# Power.net
KiCad netlist of a schematic drawn in Altium Designer
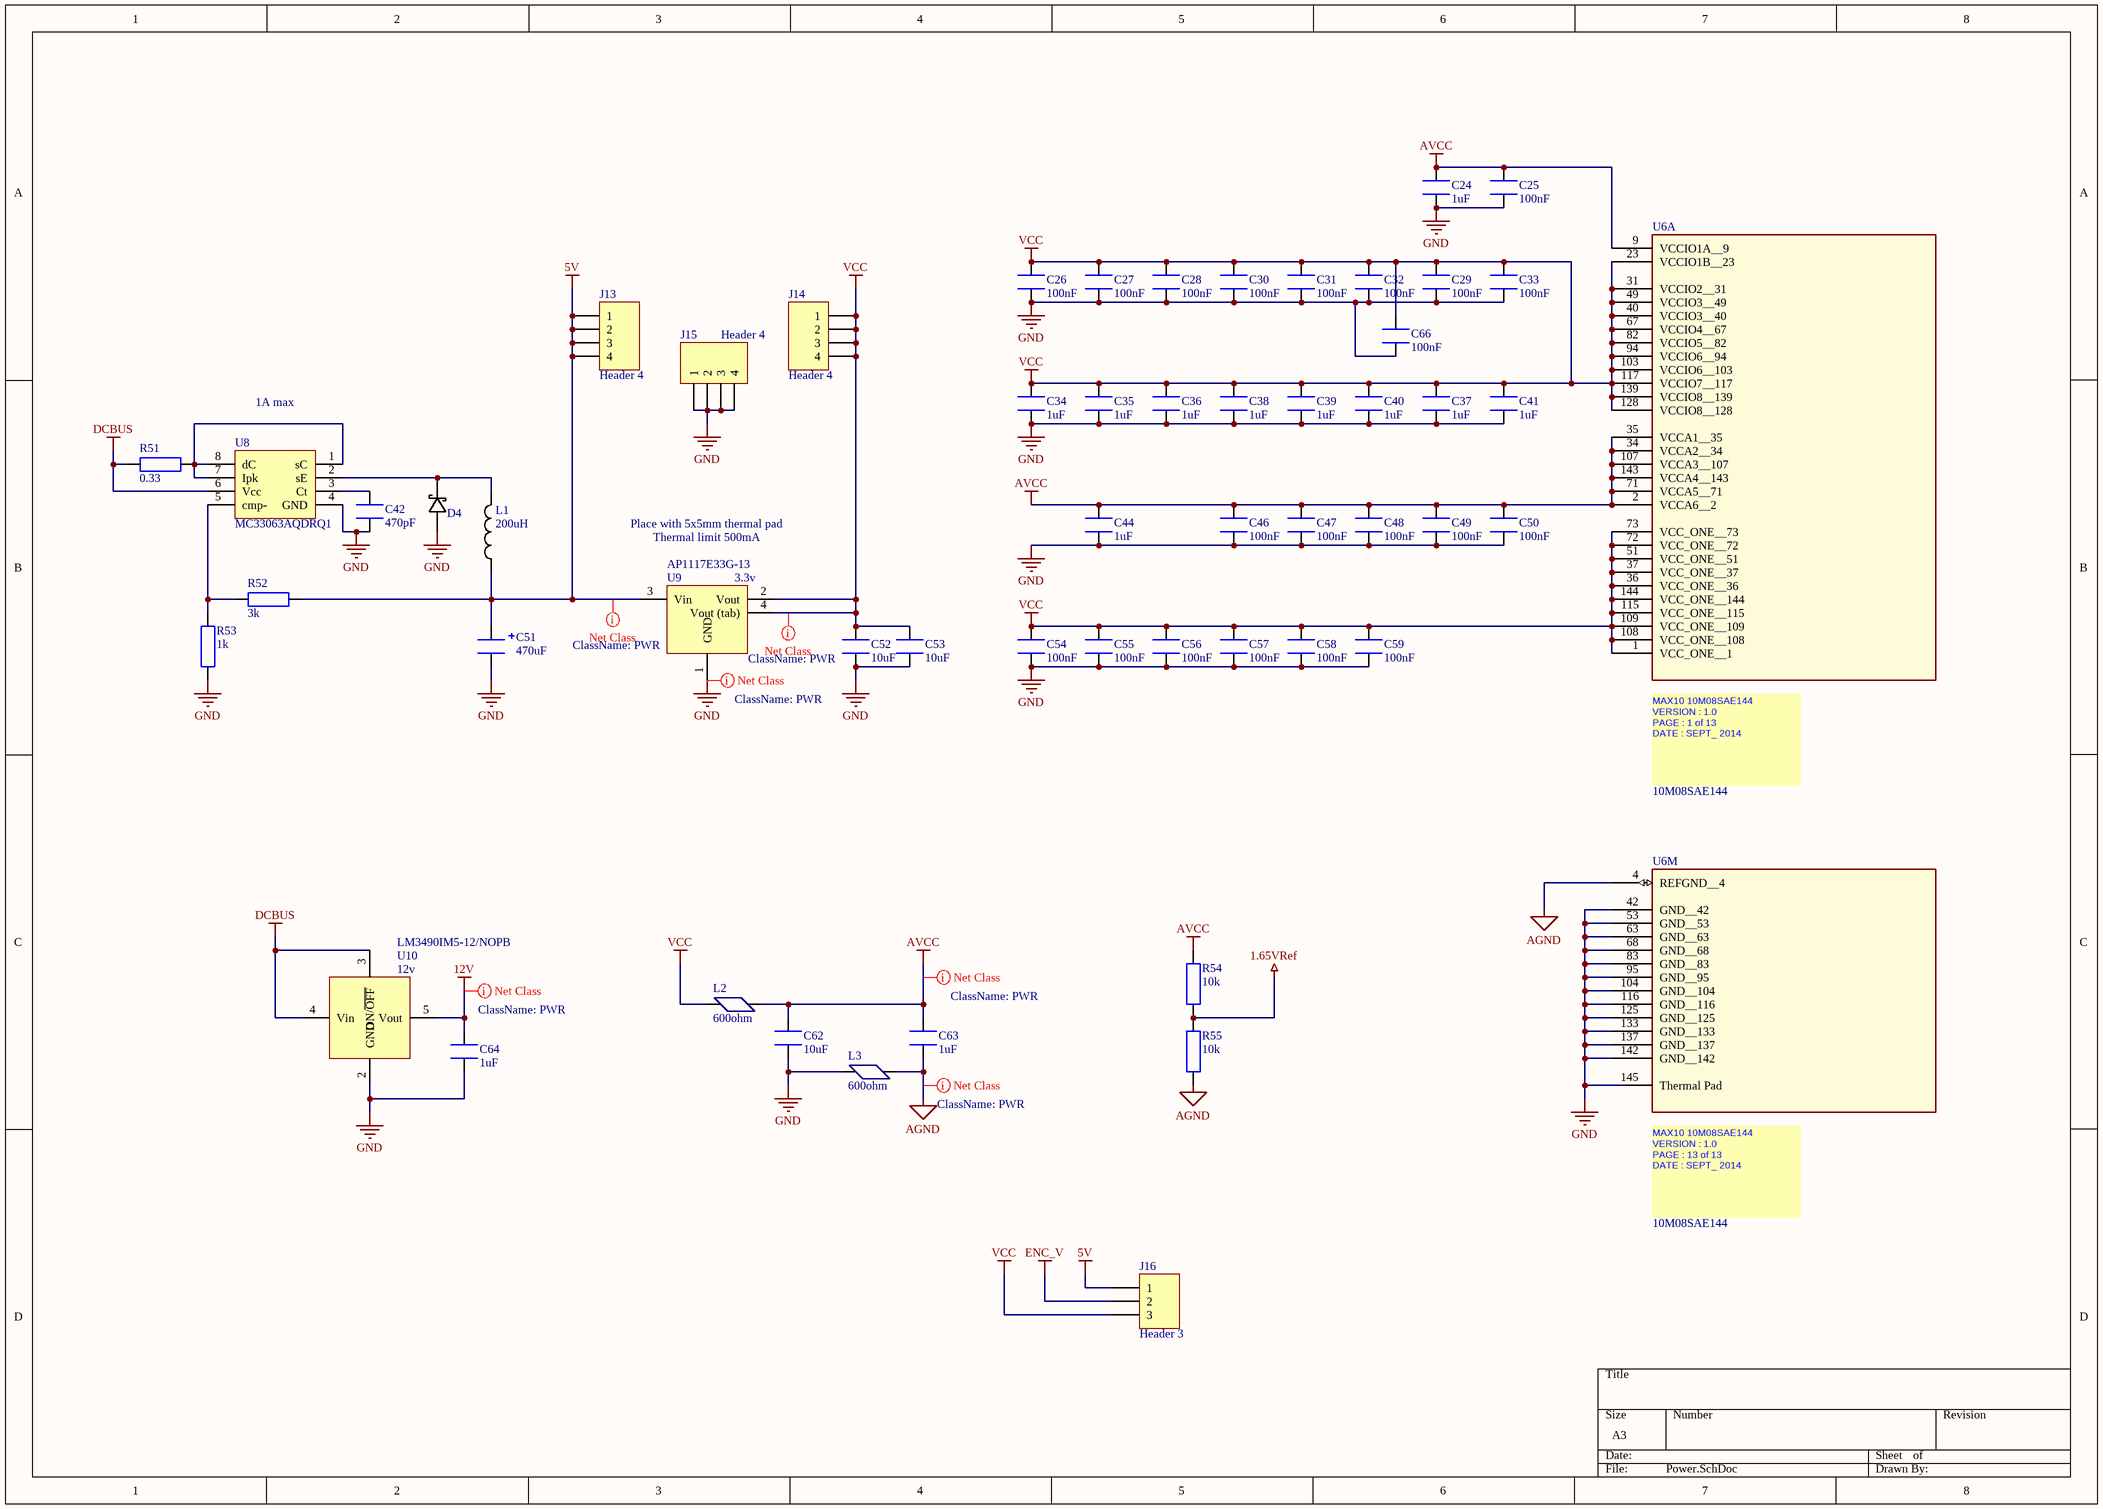
[diagram p0: Power.SchDoc]

(export (version "E")
  (design (tool "Eeschema 10.0.6"))
  (components
    (comp (ref "C24")
      (value "1uF")
      (footprint "1608[0603]")
      (description "CAP, MLCC, X5R, 1UF, 16V, 0603")
      (fields (field (name "Comment") "MC0603X105K160"))
      (libsource (lib "CustomComponents") (part "MC0603X105K160"))
    )
    (comp (ref "C25")
      (value "100nF")
      (footprint "1608[0603]")
      (description "CAP, MLCC, X7R, 100NF, 16V, 0603")
      (fields (field (name "Comment") "MC0603B104K160CT"))
      (libsource (lib "CustomComponents") (part "MC0603B104K160CT"))
    )
    (comp (ref "C26")
      (value "100nF")
      (footprint "1608[0603]")
      (description "CAP, MLCC, X7R, 100NF, 16V, 0603")
      (fields (field (name "Comment") "MC0603B104K160CT"))
      (libsource (lib "CustomComponents") (part "MC0603B104K160CT"))
    )
    (comp (ref "C27")
      (value "100nF")
      (footprint "1608[0603]")
      (description "CAP, MLCC, X7R, 100NF, 16V, 0603")
      (fields (field (name "Comment") "MC0603B104K160CT"))
      (libsource (lib "CustomComponents") (part "MC0603B104K160CT"))
    )
    (comp (ref "C28")
      (value "100nF")
      (footprint "1608[0603]")
      (description "CAP, MLCC, X7R, 100NF, 16V, 0603")
      (fields (field (name "Comment") "MC0603B104K160CT"))
      (libsource (lib "CustomComponents") (part "MC0603B104K160CT"))
    )
    (comp (ref "C29")
      (value "100nF")
      (footprint "1608[0603]")
      (description "CAP, MLCC, X7R, 100NF, 16V, 0603")
      (fields (field (name "Comment") "MC0603B104K160CT"))
      (libsource (lib "CustomComponents") (part "MC0603B104K160CT"))
    )
    (comp (ref "C30")
      (value "100nF")
      (footprint "1608[0603]")
      (description "CAP, MLCC, X7R, 100NF, 16V, 0603")
      (fields (field (name "Comment") "MC0603B104K160CT"))
      (libsource (lib "CustomComponents") (part "MC0603B104K160CT"))
    )
    (comp (ref "C31")
      (value "100nF")
      (footprint "1608[0603]")
      (description "CAP, MLCC, X7R, 100NF, 16V, 0603")
      (fields (field (name "Comment") "MC0603B104K160CT"))
      (libsource (lib "CustomComponents") (part "MC0603B104K160CT"))
    )
    (comp (ref "C32")
      (value "100nF")
      (footprint "1608[0603]")
      (description "CAP, MLCC, X7R, 100NF, 16V, 0603")
      (fields (field (name "Comment") "MC0603B104K160CT"))
      (libsource (lib "CustomComponents") (part "MC0603B104K160CT"))
    )
    (comp (ref "C33")
      (value "100nF")
      (footprint "1608[0603]")
      (description "CAP, MLCC, X7R, 100NF, 16V, 0603")
      (fields (field (name "Comment") "MC0603B104K160CT"))
      (libsource (lib "CustomComponents") (part "MC0603B104K160CT"))
    )
    (comp (ref "C34")
      (value "1uF")
      (footprint "1608[0603]")
      (description "CAP, MLCC, X5R, 1UF, 16V, 0603")
      (fields (field (name "Comment") "MC0603X105K160"))
      (libsource (lib "CustomComponents") (part "MC0603X105K160"))
    )
    (comp (ref "C35")
      (value "1uF")
      (footprint "1608[0603]")
      (description "CAP, MLCC, X5R, 1UF, 16V, 0603")
      (fields (field (name "Comment") "MC0603X105K160"))
      (libsource (lib "CustomComponents") (part "MC0603X105K160"))
    )
    (comp (ref "C36")
      (value "1uF")
      (footprint "1608[0603]")
      (description "CAP, MLCC, X5R, 1UF, 16V, 0603")
      (fields (field (name "Comment") "MC0603X105K160"))
      (libsource (lib "CustomComponents") (part "MC0603X105K160"))
    )
    (comp (ref "C37")
      (value "1uF")
      (footprint "1608[0603]")
      (description "CAP, MLCC, X5R, 1UF, 16V, 0603")
      (fields (field (name "Comment") "MC0603X105K160"))
      (libsource (lib "CustomComponents") (part "MC0603X105K160"))
    )
    (comp (ref "C38")
      (value "1uF")
      (footprint "1608[0603]")
      (description "CAP, MLCC, X5R, 1UF, 16V, 0603")
      (fields (field (name "Comment") "MC0603X105K160"))
      (libsource (lib "CustomComponents") (part "MC0603X105K160"))
    )
    (comp (ref "C39")
      (value "1uF")
      (footprint "1608[0603]")
      (description "CAP, MLCC, X5R, 1UF, 16V, 0603")
      (fields (field (name "Comment") "MC0603X105K160"))
      (libsource (lib "CustomComponents") (part "MC0603X105K160"))
    )
    (comp (ref "C40")
      (value "1uF")
      (footprint "1608[0603]")
      (description "CAP, MLCC, X5R, 1UF, 16V, 0603")
      (fields (field (name "Comment") "MC0603X105K160"))
      (libsource (lib "CustomComponents") (part "MC0603X105K160"))
    )
    (comp (ref "C41")
      (value "1uF")
      (footprint "1608[0603]")
      (description "CAP, MLCC, X5R, 1UF, 16V, 0603")
      (fields (field (name "Comment") "MC0603X105K160"))
      (libsource (lib "CustomComponents") (part "MC0603X105K160"))
    )
    (comp (ref "C42")
      (value "470pF")
      (footprint "1608[0603]")
      (description "CAP, MLCC, X7R, 470PF, 50V, 0603")
      (fields (field (name "Comment") "MC0603B471K500CT"))
      (libsource (lib "CustomComponents") (part "MC0603B471K500CT"))
    )
    (comp (ref "C44")
      (value "1uF")
      (footprint "1608[0603]")
      (description "CAP, MLCC, X5R, 1UF, 16V, 0603")
      (fields (field (name "Comment") "MC0603X105K160"))
      (libsource (lib "CustomComponents") (part "MC0603X105K160"))
    )
    (comp (ref "C46")
      (value "100nF")
      (footprint "1608[0603]")
      (description "CAP, MLCC, X7R, 100NF, 16V, 0603")
      (fields (field (name "Comment") "MC0603B104K160CT"))
      (libsource (lib "CustomComponents") (part "MC0603B104K160CT"))
    )
    (comp (ref "C47")
      (value "100nF")
      (footprint "1608[0603]")
      (description "CAP, MLCC, X7R, 100NF, 16V, 0603")
      (fields (field (name "Comment") "MC0603B104K160CT"))
      (libsource (lib "CustomComponents") (part "MC0603B104K160CT"))
    )
    (comp (ref "C48")
      (value "100nF")
      (footprint "1608[0603]")
      (description "CAP, MLCC, X7R, 100NF, 16V, 0603")
      (fields (field (name "Comment") "MC0603B104K160CT"))
      (libsource (lib "CustomComponents") (part "MC0603B104K160CT"))
    )
    (comp (ref "C49")
      (value "100nF")
      (footprint "1608[0603]")
      (description "CAP, MLCC, X7R, 100NF, 16V, 0603")
      (fields (field (name "Comment") "MC0603B104K160CT"))
      (libsource (lib "CustomComponents") (part "MC0603B104K160CT"))
    )
    (comp (ref "C50")
      (value "100nF")
      (footprint "1608[0603]")
      (description "CAP, MLCC, X7R, 100NF, 16V, 0603")
      (fields (field (name "Comment") "MC0603B104K160CT"))
      (libsource (lib "CustomComponents") (part "MC0603B104K160CT"))
    )
    (comp (ref "C51")
      (value "470uF")
      (footprint "CAP_ELEC_SIZE_G")
      (description "CAP, ALU ELEC, 470UF, 16V, SMD")
      (fields (field (name "Comment") "EEE1CA471P"))
      (libsource (lib "CustomComponents") (part "EEE1CA471P"))
    )
    (comp (ref "C52")
      (value "10uF")
      (footprint "CAPC2012X135N")
      (description "CAP, MLCC, Y5V, 10UF, 0805")
      (fields (field (name "Comment") "MC0805F106Z100CT"))
      (libsource (lib "CustomComponents") (part "MC0805F106Z100CT"))
    )
    (comp (ref "C53")
      (value "10uF")
      (footprint "CAPC2012X135N")
      (description "CAP, MLCC, Y5V, 10UF, 0805")
      (fields (field (name "Comment") "MC0805F106Z100CT"))
      (libsource (lib "CustomComponents") (part "MC0805F106Z100CT"))
    )
    (comp (ref "C54")
      (value "100nF")
      (footprint "1608[0603]")
      (description "CAP, MLCC, X7R, 100NF, 16V, 0603")
      (fields (field (name "Comment") "MC0603B104K160CT"))
      (libsource (lib "CustomComponents") (part "MC0603B104K160CT"))
    )
    (comp (ref "C55")
      (value "100nF")
      (footprint "1608[0603]")
      (description "CAP, MLCC, X7R, 100NF, 16V, 0603")
      (fields (field (name "Comment") "MC0603B104K160CT"))
      (libsource (lib "CustomComponents") (part "MC0603B104K160CT"))
    )
    (comp (ref "C56")
      (value "100nF")
      (footprint "1608[0603]")
      (description "CAP, MLCC, X7R, 100NF, 16V, 0603")
      (fields (field (name "Comment") "MC0603B104K160CT"))
      (libsource (lib "CustomComponents") (part "MC0603B104K160CT"))
    )
    (comp (ref "C57")
      (value "100nF")
      (footprint "1608[0603]")
      (description "CAP, MLCC, X7R, 100NF, 16V, 0603")
      (fields (field (name "Comment") "MC0603B104K160CT"))
      (libsource (lib "CustomComponents") (part "MC0603B104K160CT"))
    )
    (comp (ref "C58")
      (value "100nF")
      (footprint "1608[0603]")
      (description "CAP, MLCC, X7R, 100NF, 16V, 0603")
      (fields (field (name "Comment") "MC0603B104K160CT"))
      (libsource (lib "CustomComponents") (part "MC0603B104K160CT"))
    )
    (comp (ref "C59")
      (value "100nF")
      (footprint "1608[0603]")
      (description "CAP, MLCC, X7R, 100NF, 16V, 0603")
      (fields (field (name "Comment") "MC0603B104K160CT"))
      (libsource (lib "CustomComponents") (part "MC0603B104K160CT"))
    )
    (comp (ref "C62")
      (value "10uF")
      (footprint "CAPC2012X135N")
      (description "CAP, MLCC, Y5V, 10UF, 0805")
      (fields (field (name "Comment") "MC0805F106Z100CT"))
      (libsource (lib "CustomComponents") (part "MC0805F106Z100CT"))
    )
    (comp (ref "C63")
      (value "1uF")
      (footprint "1608[0603]")
      (description "CAP, MLCC, X5R, 1UF, 16V, 0603")
      (fields (field (name "Comment") "MC0603X105K160"))
      (libsource (lib "CustomComponents") (part "MC0603X105K160"))
    )
    (comp (ref "C64")
      (value "1uF")
      (footprint "1608[0603]")
      (description "CAP, MLCC, X5R, 1UF, 16V, 0603")
      (fields (field (name "Comment") "MC0603X105K160"))
      (libsource (lib "CustomComponents") (part "MC0603X105K160"))
    )
    (comp (ref "C66")
      (value "100nF")
      (footprint "1608[0603]")
      (description "CAP, MLCC, X7R, 100NF, 16V, 0603")
      (fields (field (name "Comment") "MC0603B104K160CT"))
      (libsource (lib "CustomComponents") (part "MC0603B104K160CT"))
    )
    (comp (ref "D4")
      (value "SS13B")
      (footprint "DO-214AA")
      (description "DIODE, SCHOTTK, RECTIF, 1A, 30V, SMB")
      (libsource (lib "CustomComponents") (part "SS13B"))
    )
    (comp (ref "J13")
      (value "Header 4")
      (footprint "HDR1X4")
      (description "Header, 4-Pin")
      (fields (field (name "PUBLISHER") "Altium Limited"))
      (libsource (lib "") (part "Header 4_1"))
    )
    (comp (ref "J14")
      (value "Header 4")
      (footprint "HDR1X4")
      (description "Header, 4-Pin")
      (fields (field (name "PUBLISHER") "Altium Limited"))
      (libsource (lib "") (part "Header 4_2"))
    )
    (comp (ref "J15")
      (value "Header 4")
      (footprint "HDR1X4")
      (description "Header, 4-Pin")
      (fields (field (name "PUBLISHER") "Altium Limited"))
      (libsource (lib "Miscellaneous Connectors") (part "Header 4"))
    )
    (comp (ref "J16")
      (value "Header 3")
      (footprint "HDR1X3")
      (description "Header, 3-Pin")
      (fields (field (name "PUBLISHER") "Altium Limited"))
      (libsource (lib "Miscellaneous Connectors") (part "Header 3"))
    )
    (comp (ref "L1")
      (value "200uH")
      (footprint "Inductor 12x12mm")
      (description "INDUCTOR, 220µH, 20%, 2PINS")
      (fields (field (name "Comment") "MCSDRH125B-221MHF"))
      (libsource (lib "CustomComponents") (part "MCSDRH125B-221MHF"))
    )
    (comp (ref "L2")
      (value "600ohm")
      (footprint "FBC2012N")
      (description "FERRITE BEAD, 0.1OHM, 2A, 0805")
      (fields (field (name "Comment") "2508056017Y2"))
      (libsource (lib "CustomComponents") (part "2508056017Y2"))
    )
    (comp (ref "L3")
      (value "600ohm")
      (footprint "FBC2012N")
      (description "FERRITE BEAD, 0.1OHM, 2A, 0805")
      (fields (field (name "Comment") "2508056017Y2"))
      (libsource (lib "CustomComponents") (part "2508056017Y2"))
    )
    (comp (ref "R51")
      (value "0.33")
      (footprint "RESC1608X55N")
      (description "RESISTOR, 0603, 0.1W, 1%, 0R33")
      (fields (field (name "Comment") "ERJ3RQFR33V"))
      (libsource (lib "CustomComponents") (part "ERJ3RQFR33V"))
    )
    (comp (ref "R52")
      (value "3k")
      (footprint "RESC1608X55N")
      (description "RESISTOR, 0603, 3K, 1%, ANTI SULFUR")
      (fields (field (name "Comment") "MCMR06X3001FTL"))
      (libsource (lib "CustomComponents") (part "MCMR06X3001FTL"))
    )
    (comp (ref "R53")
      (value "1k")
      (footprint "RESC1608X55N")
      (description "RESISTOR, CERAMIC, 1K, 0.1W, 1%")
      (fields (field (name "Comment") "MCMR06X1001FTL"))
      (libsource (lib "CustomComponents") (part "MCMR06X1001FTL"))
    )
    (comp (ref "R54")
      (value "10k")
      (footprint "RESC1608X06L")
      (description "Resistor, 10k, 0603")
      (fields (field (name "Comment") "MCMR06X1002FTL"))
      (libsource (lib "CustomComponents") (part "MCMR06X1002FTL"))
    )
    (comp (ref "R55")
      (value "10k")
      (footprint "RESC1608X06L")
      (description "Resistor, 10k, 0603")
      (fields (field (name "Comment") "MCMR06X1002FTL"))
      (libsource (lib "CustomComponents") (part "MCMR06X1002FTL"))
    )
    (comp (ref "U6")
      (value "10M08SAE144")
      (footprint "SQFP50P2200X2200X165_HS-145N")
      (libsource (lib "10M08SAREVERSIONTEST_Library") (part "10M08SAE144"))
    )
    (comp (ref "U8")
      (value "MC33063AQDRQ1")
      (footprint "SO8_N")
      (description "DC-DC CONV, BOOST/BUCK/INVERTING, SOIC-8")
      (libsource (lib "CustomComponents") (part "MC33063AQDRQ1"))
    )
    (comp (ref "U9")
      (value "AP1117E33G-13")
      (footprint "SOT223")
      (description "IC, LDO, REG, 3.3V, SOT223")
      (fields (field (name "ALTIUM_VALUE") "3.3v"))
      (libsource (lib "CustomComponents") (part "AP1117E33G-13"))
    )
    (comp (ref "U10")
      (value "LM3490IM5-12/NOPB")
      (footprint "SOT23-5")
      (description "LDO, FIXED, 12V, 0.1A, SOT-23-5")
      (fields (field (name "ALTIUM_VALUE") "12v"))
      (libsource (lib "CustomComponents") (part "LM3490IM5-12/NOPB"))
    )
  )
  (nets
    (net (code "1") (name "1.65VRef") (class "Default")
      (node (ref "R54") (pin "1") (pinfunction "0_1") (pintype "passive"))
      (node (ref "R55") (pin "2") (pinfunction "0_2") (pintype "passive"))
    )
    (net (code "2") (name "5V") (class "Default")
      (node (ref "C51") (pin "1") (pinfunction "1_1") (pintype "passive"))
      (node (ref "J13") (pin "1") (pinfunction "1_1") (pintype "passive"))
      (node (ref "J13") (pin "2") (pinfunction "2_2") (pintype "passive"))
      (node (ref "J13") (pin "3") (pinfunction "3_3") (pintype "passive"))
      (node (ref "J13") (pin "4") (pinfunction "4_4") (pintype "passive"))
      (node (ref "J16") (pin "1") (pinfunction "1_1") (pintype "passive"))
      (node (ref "L1") (pin "1") (pinfunction "1_1") (pintype "passive"))
      (node (ref "R52") (pin "1") (pinfunction "0_1") (pintype "passive"))
      (node (ref "U9") (pin "3") (pinfunction "Vin_3") (pintype "passive"))
    )
    (net (code "3") (name "12V") (class "Default")
      (node (ref "C64") (pin "2") (pinfunction "2_2") (pintype "passive"))
      (node (ref "U10") (pin "5") (pinfunction "Vout_5") (pintype "passive"))
    )
    (net (code "4") (name "AGND") (class "Default")
      (node (ref "C63") (pin "1") (pinfunction "1_1") (pintype "passive"))
      (node (ref "L3") (pin "1") (pinfunction "1_1") (pintype "passive"))
      (node (ref "R55") (pin "1") (pinfunction "0_1") (pintype "passive"))
      (node (ref "U6") (pin "4") (pinfunction "REFGND__4_4") (pintype "bidirectional"))
    )
    (net (code "5") (name "AVCC") (class "Default")
      (node (ref "C24") (pin "2") (pinfunction "2_2") (pintype "passive"))
      (node (ref "C25") (pin "2") (pinfunction "2_2") (pintype "passive"))
      (node (ref "C44") (pin "2") (pinfunction "2_2") (pintype "passive"))
      (node (ref "C46") (pin "2") (pinfunction "2_2") (pintype "passive"))
      (node (ref "C47") (pin "2") (pinfunction "2_2") (pintype "passive"))
      (node (ref "C48") (pin "2") (pinfunction "2_2") (pintype "passive"))
      (node (ref "C49") (pin "2") (pinfunction "2_2") (pintype "passive"))
      (node (ref "C50") (pin "2") (pinfunction "2_2") (pintype "passive"))
      (node (ref "C62") (pin "2") (pinfunction "2_2") (pintype "passive"))
      (node (ref "C63") (pin "2") (pinfunction "2_2") (pintype "passive"))
      (node (ref "L2") (pin "1") (pinfunction "1_1") (pintype "passive"))
      (node (ref "R54") (pin "2") (pinfunction "0_2") (pintype "passive"))
      (node (ref "U6") (pin "107") (pinfunction "VCCA3__107_107") (pintype "power_in"))
      (node (ref "U6") (pin "143") (pinfunction "VCCA4__143_143") (pintype "power_in"))
      (node (ref "U6") (pin "2") (pinfunction "VCCA6__2_2") (pintype "power_in"))
      (node (ref "U6") (pin "34") (pinfunction "VCCA2__34_34") (pintype "power_in"))
      (node (ref "U6") (pin "35") (pinfunction "VCCA1__35_35") (pintype "power_in"))
      (node (ref "U6") (pin "71") (pinfunction "VCCA5__71_71") (pintype "power_in"))
      (node (ref "U6") (pin "9") (pinfunction "VCCIO1A__9_9") (pintype "power_in"))
    )
    (net (code "6") (name "DCBUS") (class "Default")
      (node (ref "R51") (pin "2") (pinfunction "0_2") (pintype "passive"))
      (node (ref "U10") (pin "3") (pinfunction "ON/~{OFF}_3") (pintype "passive"))
      (node (ref "U10") (pin "4") (pinfunction "Vin_4") (pintype "passive"))
      (node (ref "U8") (pin "6") (pinfunction "Vcc_6") (pintype "passive"))
    )
    (net (code "7") (name "ENC_V") (class "Default")
      (node (ref "J16") (pin "2") (pinfunction "2_2") (pintype "passive"))
    )
    (net (code "8") (name "GND") (class "Default")
      (node (ref "C24") (pin "1") (pinfunction "1_1") (pintype "passive"))
      (node (ref "C25") (pin "1") (pinfunction "1_1") (pintype "passive"))
      (node (ref "C26") (pin "1") (pinfunction "1_1") (pintype "passive"))
      (node (ref "C27") (pin "1") (pinfunction "1_1") (pintype "passive"))
      (node (ref "C28") (pin "1") (pinfunction "1_1") (pintype "passive"))
      (node (ref "C29") (pin "1") (pinfunction "1_1") (pintype "passive"))
      (node (ref "C30") (pin "1") (pinfunction "1_1") (pintype "passive"))
      (node (ref "C31") (pin "1") (pinfunction "1_1") (pintype "passive"))
      (node (ref "C32") (pin "1") (pinfunction "1_1") (pintype "passive"))
      (node (ref "C33") (pin "1") (pinfunction "1_1") (pintype "passive"))
      (node (ref "C34") (pin "1") (pinfunction "1_1") (pintype "passive"))
      (node (ref "C35") (pin "1") (pinfunction "1_1") (pintype "passive"))
      (node (ref "C36") (pin "1") (pinfunction "1_1") (pintype "passive"))
      (node (ref "C37") (pin "1") (pinfunction "1_1") (pintype "passive"))
      (node (ref "C38") (pin "1") (pinfunction "1_1") (pintype "passive"))
      (node (ref "C39") (pin "1") (pinfunction "1_1") (pintype "passive"))
      (node (ref "C40") (pin "1") (pinfunction "1_1") (pintype "passive"))
      (node (ref "C41") (pin "1") (pinfunction "1_1") (pintype "passive"))
      (node (ref "C42") (pin "1") (pinfunction "1_1") (pintype "passive"))
      (node (ref "C44") (pin "1") (pinfunction "1_1") (pintype "passive"))
      (node (ref "C46") (pin "1") (pinfunction "1_1") (pintype "passive"))
      (node (ref "C47") (pin "1") (pinfunction "1_1") (pintype "passive"))
      (node (ref "C48") (pin "1") (pinfunction "1_1") (pintype "passive"))
      (node (ref "C49") (pin "1") (pinfunction "1_1") (pintype "passive"))
      (node (ref "C50") (pin "1") (pinfunction "1_1") (pintype "passive"))
      (node (ref "C51") (pin "2") (pinfunction "2_2") (pintype "passive"))
      (node (ref "C52") (pin "1") (pinfunction "1_1") (pintype "passive"))
      (node (ref "C53") (pin "1") (pinfunction "1_1") (pintype "passive"))
      (node (ref "C54") (pin "1") (pinfunction "1_1") (pintype "passive"))
      (node (ref "C55") (pin "1") (pinfunction "1_1") (pintype "passive"))
      (node (ref "C56") (pin "1") (pinfunction "1_1") (pintype "passive"))
      (node (ref "C57") (pin "1") (pinfunction "1_1") (pintype "passive"))
      (node (ref "C58") (pin "1") (pinfunction "1_1") (pintype "passive"))
      (node (ref "C59") (pin "1") (pinfunction "1_1") (pintype "passive"))
      (node (ref "C62") (pin "1") (pinfunction "1_1") (pintype "passive"))
      (node (ref "C64") (pin "1") (pinfunction "1_1") (pintype "passive"))
      (node (ref "C66") (pin "1") (pinfunction "1_1") (pintype "passive"))
      (node (ref "D4") (pin "A") (pinfunction "A_A") (pintype "passive"))
      (node (ref "J15") (pin "1") (pinfunction "1_1") (pintype "passive"))
      (node (ref "J15") (pin "2") (pinfunction "2_2") (pintype "passive"))
      (node (ref "J15") (pin "3") (pinfunction "3_3") (pintype "passive"))
      (node (ref "J15") (pin "4") (pinfunction "4_4") (pintype "passive"))
      (node (ref "L3") (pin "2") (pinfunction "2_2") (pintype "passive"))
      (node (ref "R53") (pin "1") (pinfunction "0_1") (pintype "passive"))
      (node (ref "U10") (pin "2") (pinfunction "GND_2") (pintype "passive"))
      (node (ref "U6") (pin "104") (pinfunction "GND__104_104") (pintype "power_in"))
      (node (ref "U6") (pin "116") (pinfunction "GND__116_116") (pintype "power_in"))
      (node (ref "U6") (pin "125") (pinfunction "GND__125_125") (pintype "power_in"))
      (node (ref "U6") (pin "133") (pinfunction "GND__133_133") (pintype "power_in"))
      (node (ref "U6") (pin "137") (pinfunction "GND__137_137") (pintype "power_in"))
      (node (ref "U6") (pin "142") (pinfunction "GND__142_142") (pintype "power_in"))
      (node (ref "U6") (pin "145") (pinfunction "Thermal_Pad_145") (pintype "passive"))
      (node (ref "U6") (pin "42") (pinfunction "GND__42_42") (pintype "power_in"))
      (node (ref "U6") (pin "53") (pinfunction "GND__53_53") (pintype "power_in"))
      (node (ref "U6") (pin "63") (pinfunction "GND__63_63") (pintype "power_in"))
      (node (ref "U6") (pin "68") (pinfunction "GND__68_68") (pintype "power_in"))
      (node (ref "U6") (pin "83") (pinfunction "GND__83_83") (pintype "power_in"))
      (node (ref "U6") (pin "95") (pinfunction "GND__95_95") (pintype "power_in"))
      (node (ref "U8") (pin "4") (pinfunction "GND_4") (pintype "passive"))
      (node (ref "U9") (pin "1") (pinfunction "GND_1") (pintype "passive"))
    )
    (net (code "9") (name "Net-(U8-Ct)") (class "Default")
      (node (ref "C42") (pin "2") (pinfunction "2_2") (pintype "passive"))
      (node (ref "U8") (pin "3") (pinfunction "Ct_3") (pintype "passive"))
    )
    (net (code "10") (name "Net-(U8-Ipk)") (class "Default")
      (node (ref "R51") (pin "1") (pinfunction "0_1") (pintype "passive"))
      (node (ref "U8") (pin "1") (pinfunction "sC_1") (pintype "passive"))
      (node (ref "U8") (pin "7") (pinfunction "Ipk_7") (pintype "passive"))
      (node (ref "U8") (pin "8") (pinfunction "dC_8") (pintype "passive"))
    )
    (net (code "11") (name "Net-(U8-cmp-)") (class "Default")
      (node (ref "R52") (pin "2") (pinfunction "0_2") (pintype "passive"))
      (node (ref "R53") (pin "2") (pinfunction "0_2") (pintype "passive"))
      (node (ref "U8") (pin "5") (pinfunction "cmp-_5") (pintype "passive"))
    )
    (net (code "12") (name "Net-(U8-sE)") (class "Default")
      (node (ref "D4") (pin "K") (pinfunction "K_K") (pintype "passive"))
      (node (ref "L1") (pin "2") (pinfunction "2_2") (pintype "passive"))
      (node (ref "U8") (pin "2") (pinfunction "sE_2") (pintype "passive"))
    )
    (net (code "13") (name "VCC") (class "Default")
      (node (ref "C26") (pin "2") (pinfunction "2_2") (pintype "passive"))
      (node (ref "C27") (pin "2") (pinfunction "2_2") (pintype "passive"))
      (node (ref "C28") (pin "2") (pinfunction "2_2") (pintype "passive"))
      (node (ref "C29") (pin "2") (pinfunction "2_2") (pintype "passive"))
      (node (ref "C30") (pin "2") (pinfunction "2_2") (pintype "passive"))
      (node (ref "C31") (pin "2") (pinfunction "2_2") (pintype "passive"))
      (node (ref "C32") (pin "2") (pinfunction "2_2") (pintype "passive"))
      (node (ref "C33") (pin "2") (pinfunction "2_2") (pintype "passive"))
      (node (ref "C34") (pin "2") (pinfunction "2_2") (pintype "passive"))
      (node (ref "C35") (pin "2") (pinfunction "2_2") (pintype "passive"))
      (node (ref "C36") (pin "2") (pinfunction "2_2") (pintype "passive"))
      (node (ref "C37") (pin "2") (pinfunction "2_2") (pintype "passive"))
      (node (ref "C38") (pin "2") (pinfunction "2_2") (pintype "passive"))
      (node (ref "C39") (pin "2") (pinfunction "2_2") (pintype "passive"))
      (node (ref "C40") (pin "2") (pinfunction "2_2") (pintype "passive"))
      (node (ref "C41") (pin "2") (pinfunction "2_2") (pintype "passive"))
      (node (ref "C52") (pin "2") (pinfunction "2_2") (pintype "passive"))
      (node (ref "C53") (pin "2") (pinfunction "2_2") (pintype "passive"))
      (node (ref "C54") (pin "2") (pinfunction "2_2") (pintype "passive"))
      (node (ref "C55") (pin "2") (pinfunction "2_2") (pintype "passive"))
      (node (ref "C56") (pin "2") (pinfunction "2_2") (pintype "passive"))
      (node (ref "C57") (pin "2") (pinfunction "2_2") (pintype "passive"))
      (node (ref "C58") (pin "2") (pinfunction "2_2") (pintype "passive"))
      (node (ref "C59") (pin "2") (pinfunction "2_2") (pintype "passive"))
      (node (ref "C66") (pin "2") (pinfunction "2_2") (pintype "passive"))
      (node (ref "J14") (pin "1") (pinfunction "1_1") (pintype "passive"))
      (node (ref "J14") (pin "2") (pinfunction "2_2") (pintype "passive"))
      (node (ref "J14") (pin "3") (pinfunction "3_3") (pintype "passive"))
      (node (ref "J14") (pin "4") (pinfunction "4_4") (pintype "passive"))
      (node (ref "J16") (pin "3") (pinfunction "3_3") (pintype "passive"))
      (node (ref "L2") (pin "2") (pinfunction "2_2") (pintype "passive"))
      (node (ref "U6") (pin "1") (pinfunction "VCC_ONE__1_1") (pintype "power_in"))
      (node (ref "U6") (pin "103") (pinfunction "VCCIO6__103_103") (pintype "power_in"))
      (node (ref "U6") (pin "108") (pinfunction "VCC_ONE__108_108") (pintype "power_in"))
      (node (ref "U6") (pin "109") (pinfunction "VCC_ONE__109_109") (pintype "power_in"))
      (node (ref "U6") (pin "115") (pinfunction "VCC_ONE__115_115") (pintype "power_in"))
      (node (ref "U6") (pin "117") (pinfunction "VCCIO7__117_117") (pintype "power_in"))
      (node (ref "U6") (pin "128") (pinfunction "VCCIO8__128_128") (pintype "power_in"))
      (node (ref "U6") (pin "139") (pinfunction "VCCIO8__139_139") (pintype "power_in"))
      (node (ref "U6") (pin "144") (pinfunction "VCC_ONE__144_144") (pintype "power_in"))
      (node (ref "U6") (pin "23") (pinfunction "VCCIO1B__23_23") (pintype "power_in"))
      (node (ref "U6") (pin "31") (pinfunction "VCCIO2__31_31") (pintype "power_in"))
      (node (ref "U6") (pin "36") (pinfunction "VCC_ONE__36_36") (pintype "power_in"))
      (node (ref "U6") (pin "37") (pinfunction "VCC_ONE__37_37") (pintype "power_in"))
      (node (ref "U6") (pin "40") (pinfunction "VCCIO3__40_40") (pintype "power_in"))
      (node (ref "U6") (pin "49") (pinfunction "VCCIO3__49_49") (pintype "power_in"))
      (node (ref "U6") (pin "51") (pinfunction "VCC_ONE__51_51") (pintype "power_in"))
      (node (ref "U6") (pin "67") (pinfunction "VCCIO4__67_67") (pintype "power_in"))
      (node (ref "U6") (pin "72") (pinfunction "VCC_ONE__72_72") (pintype "power_in"))
      (node (ref "U6") (pin "73") (pinfunction "VCC_ONE__73_73") (pintype "power_in"))
      (node (ref "U6") (pin "82") (pinfunction "VCCIO5__82_82") (pintype "power_in"))
      (node (ref "U6") (pin "94") (pinfunction "VCCIO6__94_94") (pintype "power_in"))
      (node (ref "U9") (pin "2") (pinfunction "Vout_2") (pintype "passive"))
      (node (ref "U9") (pin "4") (pinfunction "Vout_(tab)_4") (pintype "passive"))
    )
  )
)
